# Tp_Main.net
KiCad netlist of a schematic drawn in Altium Designer
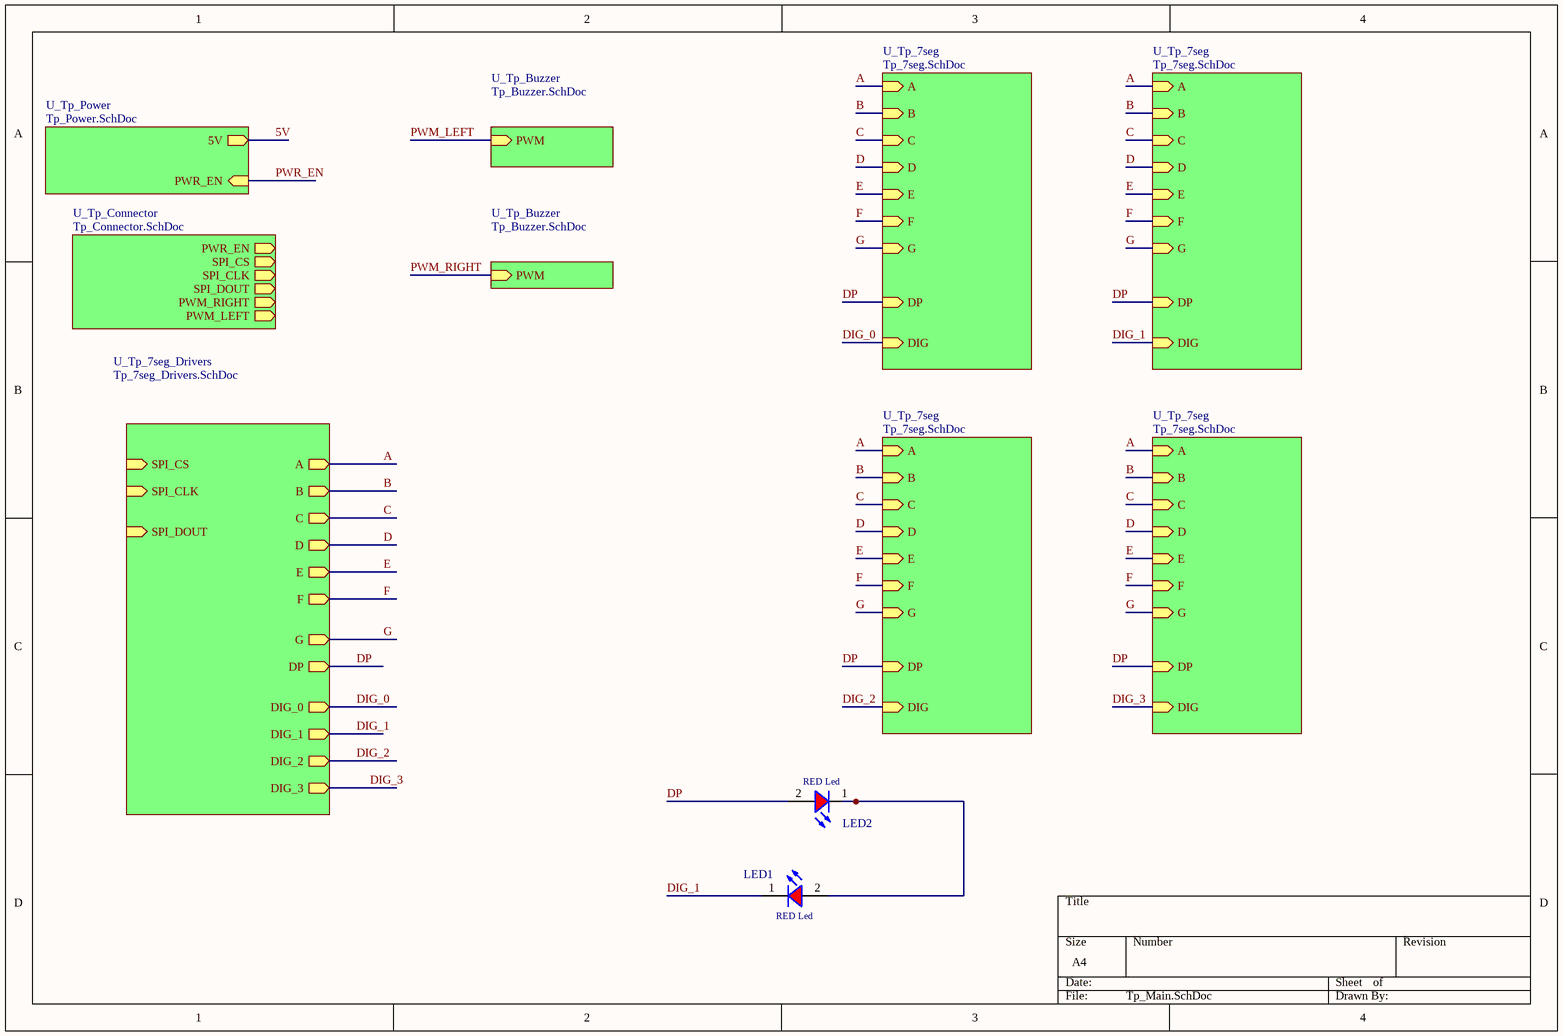
[diagram p0: Tp_Main.SchDoc]

(export (version "E")
  (design (tool "Eeschema 10.0.6"))
  (components
    (comp (ref "LED1")
      (value "RED Led")
      (footprint "LED_0603_RED")
      (description "LED RED SMD WE 150060RS750x0")
      (libsource (lib "TpGiven") (part "LED_RED_SMD_WE_150060RS750x0"))
    )
    (comp (ref "LED2")
      (value "RED Led")
      (footprint "LED_0603_RED")
      (description "LED RED SMD WE 150060RS750x0")
      (libsource (lib "TpGiven") (part "LED_RED_SMD_WE_150060RS750x0"))
    )
  )
  (nets
    (net (code "7") (name "/DIG_1") (class "Default")
      (node (ref "LED1") (pin "1") (pinfunction "K_1") (pintype "passive"))
    )
    (net (code "10") (name "/DP") (class "Default")
      (node (ref "LED2") (pin "2") (pinfunction "A_2") (pintype "passive"))
    )
    (net (code "26") (name "Net-(LED1-A)") (class "Default")
      (node (ref "LED1") (pin "2") (pinfunction "A_2") (pintype "passive"))
      (node (ref "LED2") (pin "1") (pinfunction "K_1") (pintype "passive"))
    )
  )
)
